# current_sense.net
KiCad netlist of a schematic drawn in Altium Designer
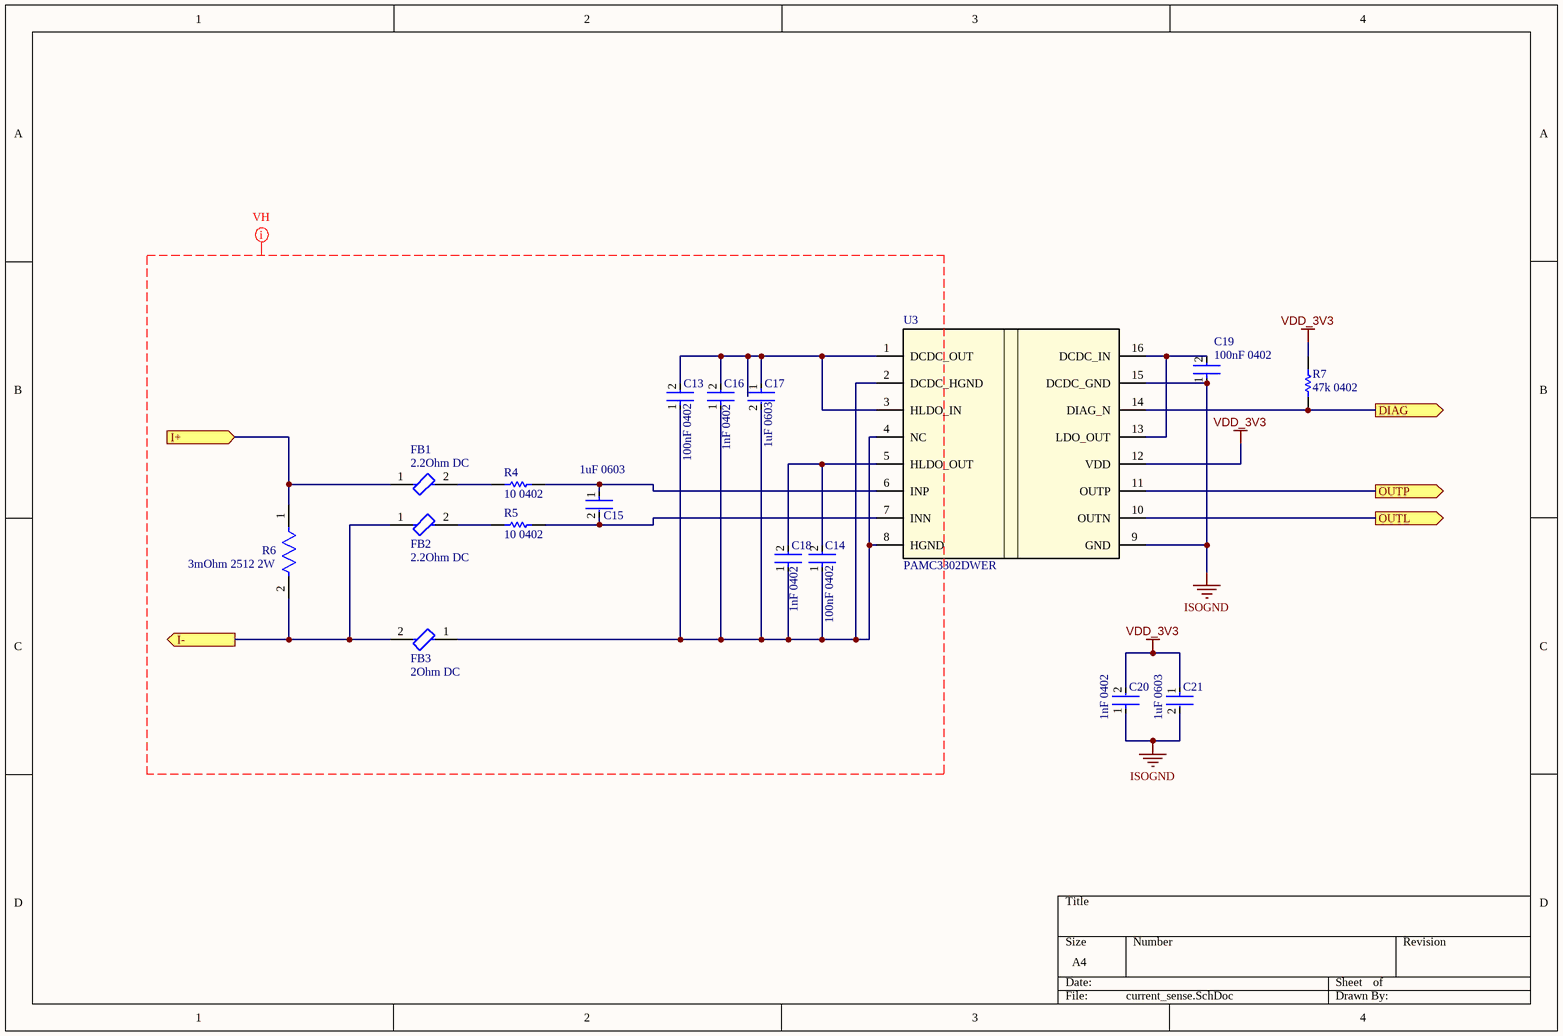
[diagram p0: current_sense.SchDoc]

(export (version "E")
  (design (tool "Eeschema 10.0.6"))
  (components
    (comp (ref "C13")
      (value "100nF 0402")
      (footprint "CAP 0402_1005 RF")
      (description "MLCC 0402 100nF")
      (fields (field (name "VOLTAGE") "50V") (field (name "TOLERANCE") "5%"))
      (libsource (lib "mdriver2_control") (part "b4654b650e69147ec39a6b967a45e02"))
    )
    (comp (ref "C14")
      (value "100nF 0402")
      (footprint "CAP 0402_1005 RF")
      (description "MLCC 0402 100nF")
      (fields (field (name "VOLTAGE") "50V") (field (name "TOLERANCE") "5%"))
      (libsource (lib "mdriver2_control") (part "b4654b650e69147ec39a6b967a45e02"))
    )
    (comp (ref "C15")
      (value "1uF 0603")
      (footprint "CAP 0603_1608")
      (description "MLCC 0402 100pF")
      (fields (field (name "VOLTAGE") "50V") (field (name "TOLERANCE") "5%"))
      (libsource (lib "mdriver2_control") (part "b4654b650e69147ec39a6b967a45e02"))
    )
    (comp (ref "C16")
      (value "1nF 0402")
      (footprint "CAP 0402_1005 RF")
      (description "MLCC 0402 1nF")
      (fields (field (name "VOLTAGE") "50V") (field (name "TOLERANCE") "5%"))
      (libsource (lib "mdriver2_control") (part "b4654b650e69147ec39a6b967a45e02"))
    )
    (comp (ref "C17")
      (value "1uF 0603")
      (footprint "CAP 0603_1608")
      (description "MLCC 0603 1uF")
      (fields (field (name "VOLTAGE") "50V") (field (name "TOLERANCE") "5%"))
      (libsource (lib "mdriver2_control") (part "b4654b650e69147ec39a6b967a45e02"))
    )
    (comp (ref "C18")
      (value "1nF 0402")
      (footprint "CAP 0402_1005 RF")
      (description "MLCC 0402 1nF")
      (fields (field (name "VOLTAGE") "50V") (field (name "TOLERANCE") "5%"))
      (libsource (lib "mdriver2_control") (part "b4654b650e69147ec39a6b967a45e02"))
    )
    (comp (ref "C19")
      (value "100nF 0402")
      (footprint "CAP 0402_1005 RF")
      (description "MLCC 0402 100nF")
      (fields (field (name "VOLTAGE") "50V") (field (name "TOLERANCE") "5%"))
      (libsource (lib "mdriver2_control") (part "b4654b650e69147ec39a6b967a45e02"))
    )
    (comp (ref "C20")
      (value "1nF 0402")
      (footprint "CAP 0402_1005 RF")
      (description "MLCC 0402 1nF")
      (fields (field (name "VOLTAGE") "50V") (field (name "TOLERANCE") "5%"))
      (libsource (lib "mdriver2_control") (part "b4654b650e69147ec39a6b967a45e02"))
    )
    (comp (ref "C21")
      (value "1uF 0603")
      (footprint "CAP 0603_1608")
      (description "MLCC 0603 1uF")
      (fields (field (name "VOLTAGE") "50V") (field (name "TOLERANCE") "5%"))
      (libsource (lib "mdriver2_control") (part "b4654b650e69147ec39a6b967a45e02"))
    )
    (comp (ref "FB1")
      (value "2.2Ohm DC")
      (footprint "FER 0402_1005")
      (description "Chip Ferrite Bead, 0402, 1800Ω @ 100MHz, 2.2Ω, 25%, 200mA")
      (libsource (lib "mdriver2_power_hw") (part "5f30dd21d616792df468990f7003faa"))
    )
    (comp (ref "FB2")
      (value "2.2Ohm DC")
      (footprint "FER 0402_1005")
      (description "Chip Ferrite Bead, 0402, 1800Ω @ 100MHz, 2.2Ω, 25%, 200mA")
      (libsource (lib "mdriver2_power_hw") (part "5f30dd21d616792df468990f7003faa"))
    )
    (comp (ref "FB3")
      (value "2Ohm DC")
      (footprint "FP-BKH1005-MFG")
      (description "1.8 kOhms @ 100 MHz 1 Ferrite Bead 0402 (1005 Metric) 200mA 2Ohm")
      (fields (field (name "TOLERANCE") "25%"))
      (libsource (lib "Altium Content Vault") (part "5f30dd21d616792df468990f7003faa"))
    )
    (comp (ref "R4")
      (value "10 0402")
      (footprint "RES 0402_1005")
      (description "Resistor 10Ohm 0603")
      (fields (field (name "PUBLISHER") "Altium Limited"))
      (libsource (lib "Miscellaneous Devices") (part "Res1"))
    )
    (comp (ref "R5")
      (value "10 0402")
      (footprint "RES 0402_1005")
      (description "Resistor 10Ohm 0603")
      (fields (field (name "PUBLISHER") "Altium Limited"))
      (libsource (lib "Miscellaneous Devices") (part "Res1"))
    )
    (comp (ref "R6")
      (value "3mOhm 2512 2W")
      (footprint "FP-CSNL2512-MFG")
      (description "RES 0.003 OHM 1% 2W 2512")
      (fields
        (field (name "OCTOPART") "https://octopart.com/csnl2512ft3l00-stackpole+electronics-19206420")
        (field (name "3DS PART NUMBER") "110-00007")
      )
      (libsource (lib "Altium Content Vault") (part "1029c3af85768c4190bb7ad29bc67b5"))
    )
    (comp (ref "R7")
      (value "47k 0402")
      (footprint "RES 0402_1005")
      (description "Resistor 47kOhm 0402")
      (fields (field (name "PUBLISHER") "Altium Limited"))
      (libsource (lib "Miscellaneous Devices") (part "Res1"))
    )
    (comp (ref "U3")
      (value "PAMC3302DWER")
      (footprint "DWE0016A-IPC_A")
      (fields (field (name "COPYRIGHT") "Copyright (C) 2025 Ultra Librarian. All rights reserved."))
      (libsource (lib "PAMC3302DWER") (part "PAMC3302DWER"))
    )
  )
  (nets
    (net (code "1") (name "/DIAG") (class "Default")
      (node (ref "R7") (pin "2") (pinfunction "2_2") (pintype "passive"))
      (node (ref "U3") (pin "14") (pinfunction "DIAG_N_14") (pintype "open_collector"))
    )
    (net (code "2") (name "/I+") (class "Default")
      (node (ref "FB1") (pin "1") (pinfunction "1_1") (pintype "passive"))
      (node (ref "R6") (pin "1") (pinfunction "1_1") (pintype "passive"))
    )
    (net (code "3") (name "/I-") (class "Default")
      (node (ref "FB2") (pin "1") (pinfunction "1_1") (pintype "passive"))
      (node (ref "FB3") (pin "2") (pinfunction "2_2") (pintype "passive"))
      (node (ref "R6") (pin "2") (pinfunction "2_2") (pintype "passive"))
    )
    (net (code "4") (name "/OUTL") (class "Default")
      (node (ref "U3") (pin "10") (pinfunction "OUTN_10") (pintype "passive"))
    )
    (net (code "5") (name "/OUTP") (class "Default")
      (node (ref "U3") (pin "11") (pinfunction "OUTP_11") (pintype "passive"))
    )
    (net (code "6") (name "ISOGND") (class "Default")
      (node (ref "C19") (pin "1") (pinfunction "1_1") (pintype "passive"))
      (node (ref "C20") (pin "1") (pinfunction "1_1") (pintype "passive"))
      (node (ref "C21") (pin "2") (pinfunction "2_2") (pintype "passive"))
      (node (ref "U3") (pin "15") (pinfunction "DCDC_GND_15") (pintype "power_in"))
      (node (ref "U3") (pin "9") (pinfunction "GND_9") (pintype "power_in"))
    )
    (net (code "7") (name "Net-(FB1-Pad2)") (class "Default")
      (node (ref "FB1") (pin "2") (pinfunction "2_2") (pintype "passive"))
      (node (ref "R4") (pin "2") (pinfunction "2_2") (pintype "passive"))
    )
    (net (code "8") (name "Net-(FB2-Pad2)") (class "Default")
      (node (ref "FB2") (pin "2") (pinfunction "2_2") (pintype "passive"))
      (node (ref "R5") (pin "2") (pinfunction "2_2") (pintype "passive"))
    )
    (net (code "9") (name "Net-(U3-DCDC_HGND)") (class "Default")
      (node (ref "C13") (pin "1") (pinfunction "1_1") (pintype "passive"))
      (node (ref "C14") (pin "1") (pinfunction "1_1") (pintype "passive"))
      (node (ref "C16") (pin "1") (pinfunction "1_1") (pintype "passive"))
      (node (ref "C17") (pin "2") (pinfunction "2_2") (pintype "passive"))
      (node (ref "C18") (pin "1") (pinfunction "1_1") (pintype "passive"))
      (node (ref "FB3") (pin "1") (pinfunction "1_1") (pintype "passive"))
      (node (ref "U3") (pin "2") (pinfunction "DCDC_HGND_2") (pintype "power_in"))
      (node (ref "U3") (pin "4") (pinfunction "NC_4") (pintype "passive"))
      (node (ref "U3") (pin "8") (pinfunction "HGND_8") (pintype "power_in"))
    )
    (net (code "10") (name "Net-(U3-DCDC_IN)") (class "Default")
      (node (ref "C19") (pin "2") (pinfunction "2_2") (pintype "passive"))
      (node (ref "U3") (pin "13") (pinfunction "LDO_OUT_13") (pintype "passive"))
      (node (ref "U3") (pin "16") (pinfunction "DCDC_IN_16") (pintype "power_in"))
    )
    (net (code "11") (name "Net-(U3-DCDC_OUT)") (class "Default")
      (node (ref "C13") (pin "2") (pinfunction "2_2") (pintype "passive"))
      (node (ref "C16") (pin "2") (pinfunction "2_2") (pintype "passive"))
      (node (ref "C17") (pin "1") (pinfunction "1_1") (pintype "passive"))
      (node (ref "U3") (pin "1") (pinfunction "DCDC_OUT_1") (pintype "passive"))
      (node (ref "U3") (pin "3") (pinfunction "HLDO_IN_3") (pintype "power_in"))
    )
    (net (code "12") (name "Net-(U3-HLDO_OUT)") (class "Default")
      (node (ref "C14") (pin "2") (pinfunction "2_2") (pintype "passive"))
      (node (ref "C18") (pin "2") (pinfunction "2_2") (pintype "passive"))
      (node (ref "U3") (pin "5") (pinfunction "HLDO_OUT_5") (pintype "passive"))
    )
    (net (code "13") (name "Net-(U3-INN)") (class "Default")
      (node (ref "C15") (pin "2") (pinfunction "2_2") (pintype "passive"))
      (node (ref "R5") (pin "1") (pinfunction "1_1") (pintype "passive"))
      (node (ref "U3") (pin "7") (pinfunction "INN_7") (pintype "tri_state"))
    )
    (net (code "14") (name "Net-(U3-INP)") (class "Default")
      (node (ref "C15") (pin "1") (pinfunction "1_1") (pintype "passive"))
      (node (ref "R4") (pin "1") (pinfunction "1_1") (pintype "passive"))
      (node (ref "U3") (pin "6") (pinfunction "INP_6") (pintype "tri_state"))
    )
    (net (code "15") (name "VDD_3V3") (class "Default")
      (node (ref "C20") (pin "2") (pinfunction "2_2") (pintype "passive"))
      (node (ref "C21") (pin "1") (pinfunction "1_1") (pintype "passive"))
      (node (ref "R7") (pin "1") (pinfunction "1_1") (pintype "passive"))
      (node (ref "U3") (pin "12") (pinfunction "VDD_12") (pintype "power_in"))
    )
  )
)
